# POWER.net
KiCad netlist of a schematic drawn in Altium Designer
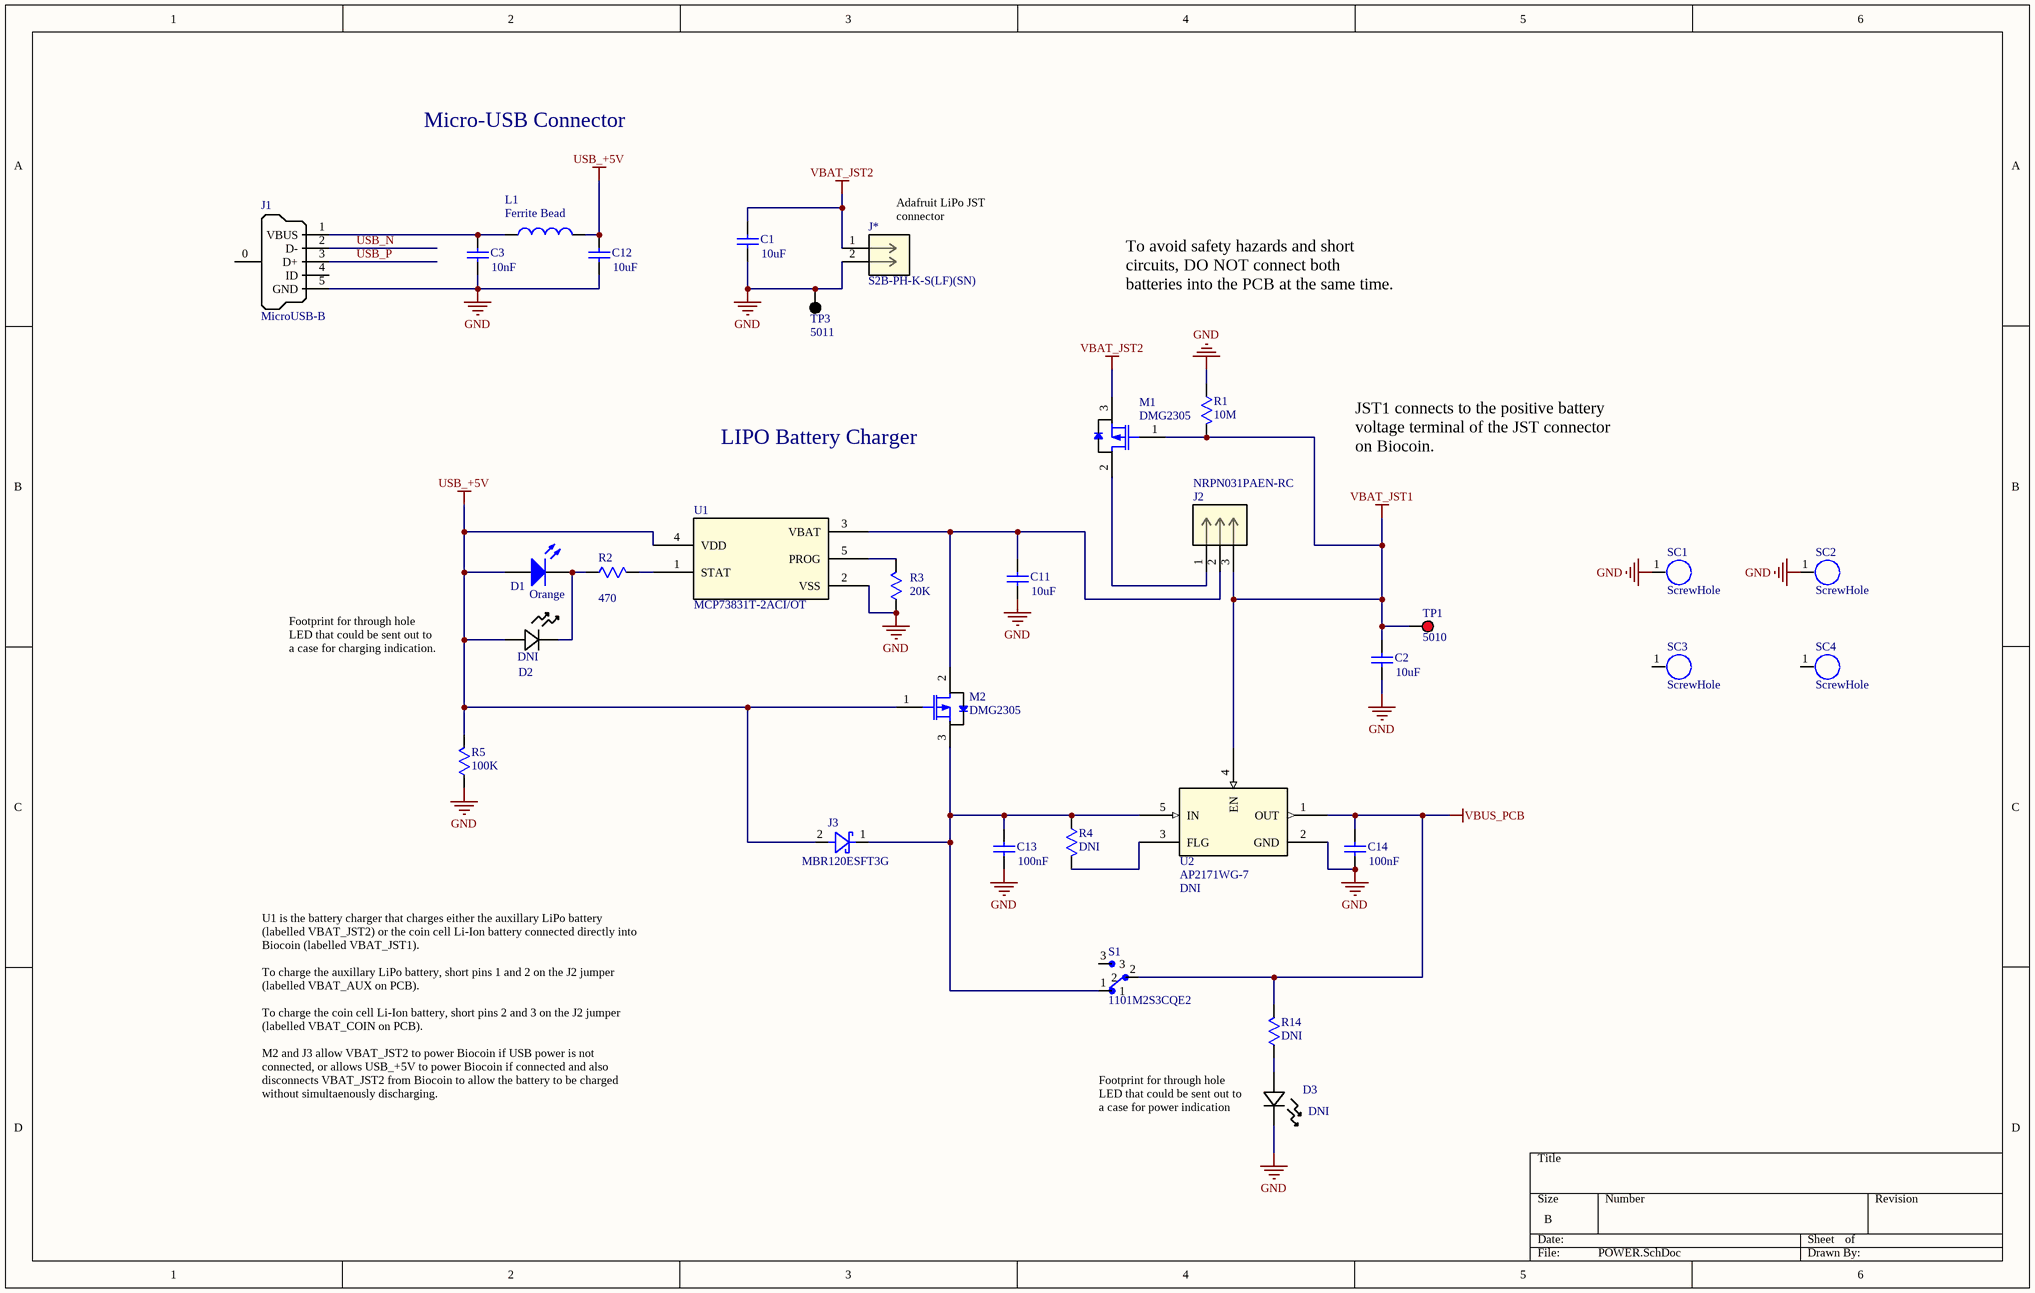
[diagram p0: POWER.SchDoc]

(export (version "E")
  (design (tool "Eeschema 10.0.6"))
  (components
    (comp (ref "C1")
      (value "10uF")
      (footprint "0805-CAP")
      (description "Multilayer Chip Capacitor")
      (fields (field (name "Comment") "CAP") (field (name "DESIGNER") "OMIGA"))
      (libsource (lib "Schlib") (part "CAP SMD"))
    )
    (comp (ref "C2")
      (value "10uF")
      (footprint "0805-CAP")
      (description "Multilayer Chip Capacitor")
      (fields (field (name "Comment") "CAP") (field (name "DESIGNER") "OMIGA"))
      (libsource (lib "Schlib") (part "CAP SMD"))
    )
    (comp (ref "C3")
      (value "10nF")
      (footprint "0805-CAP")
      (description "Multilayer Chip Capacitor")
      (fields (field (name "Comment") "CAP") (field (name "DESIGNER") "OMIGA"))
      (libsource (lib "Schlib") (part "CAP SMD"))
    )
    (comp (ref "C11")
      (value "10uF")
      (footprint "0805-CAP")
      (description "Multilayer Chip Capacitor")
      (fields (field (name "Comment") "CAP") (field (name "DESIGNER") "OMIGA"))
      (libsource (lib "Schlib") (part "CAP SMD"))
    )
    (comp (ref "C12")
      (value "10uF")
      (footprint "0805-CAP")
      (description "Multilayer Chip Capacitor")
      (fields (field (name "Comment") "CAP") (field (name "DESIGNER") "OMIGA"))
      (libsource (lib "Schlib") (part "CAP SMD"))
    )
    (comp (ref "C13")
      (value "100nF")
      (footprint "0805-CAP")
      (description "Multilayer Chip Capacitor")
      (fields (field (name "Comment") "CAP") (field (name "DESIGNER") "OMIGA"))
      (libsource (lib "Schlib") (part "CAP SMD"))
    )
    (comp (ref "C14")
      (value "100nF")
      (footprint "0805-CAP")
      (description "Multilayer Chip Capacitor")
      (fields (field (name "Comment") "CAP") (field (name "DESIGNER") "OMIGA"))
      (libsource (lib "Schlib") (part "CAP SMD"))
    )
    (comp (ref "D1")
      (value "LED SMD")
      (footprint "0805-LED")
      (description "Surface Mount Light Emitting Diode")
      (fields (field (name "LIGHT COLOR") "Orange"))
      (libsource (lib "Schlib") (part "LED SMD"))
    )
    (comp (ref "D2")
      (value "SLI-343V8RC3F")
      (footprint "LED_SLI-343D_ROM")
      (description "No Description Available")
      (fields
        (field (name "DO NOT INSTALL") "DNI")
        (field (name "COPYRIGHT") "Copyright (C) 2018 Accelerated Designs. All rights reserved")
      )
      (libsource (lib "Schlib") (part "SLI-343V8RC3F"))
    )
    (comp (ref "D3")
      (value "SLI-343V8RC3F")
      (footprint "LED_SLI-343D_ROM")
      (description "No Description Available")
      (fields
        (field (name "DO NOT INSTALL") "DNI")
        (field (name "COPYRIGHT") "Copyright (C) 2018 Accelerated Designs. All rights reserved")
      )
      (libsource (lib "Schlib") (part "SLI-343V8RC3F"))
    )
    (comp (ref "J*")
      (value "S2B-PH-K-S(LF)(SN)")
      (footprint "CONN_S2B-PH-K-S_JST")
      (description "Connector Header Through Hole, Right Angle 2 position 0.079\" (2.00mm)")
      (libsource (lib "Schlib") (part "S2B-PH-K-S(LF)(SN)"))
    )
    (comp (ref "J1")
      (value "MicroUSB-B")
      (footprint "MicroUSB-B")
      (description "Conn Micro USB Type B RCP 5")
      (fields (field (name "DESIGNER") "OMIGA"))
      (libsource (lib "Schlib") (part "MicroUSB-B"))
    )
    (comp (ref "J2")
      (value "NRPN031PAEN-RC")
      (footprint "CONN_NRPN031_SUL")
      (description "No Description Available")
      (fields (field (name "COPYRIGHT") "Copyright (C) 2022 Ultra Librarian. All rights reserved."))
      (libsource (lib "Schlib") (part "NRPN031PAEN-RC"))
    )
    (comp (ref "J3")
      (value "MBR120ESFT3G")
      (footprint "SDO_SOD-123FL_ONS-L")
      (description "Diode Schottky 1A Surface Mount SOD-123FL")
      (libsource (lib "Schlib") (part "SCHOTTKY"))
    )
    (comp (ref "L1")
      (value "Ferrite Bead")
      (footprint "0805-IND")
      (description "Surface Mount Inductor")
      (fields (field (name "Comment") "IND") (field (name "DESIGNER") "OMIGA"))
      (libsource (lib "Schlib") (part "IND SMD"))
    )
    (comp (ref "M1")
      (value "DMG2305")
      (footprint "SOT23-3-Lead")
      (description "P-Channel MOSFET DMG2305UX-13")
      (fields (field (name "DESIGNER") "OMIGA"))
      (libsource (lib "Schlib") (part "PMOS"))
    )
    (comp (ref "M2")
      (value "DMG2305")
      (footprint "SOT23-3-Lead")
      (description "P-Channel MOSFET DMG2305UX-13")
      (fields (field (name "DESIGNER") "OMIGA"))
      (libsource (lib "Schlib") (part "PMOS"))
    )
    (comp (ref "R1")
      (value "10M")
      (footprint "0805-RES")
      (description "Surface Mount Resistor")
      (fields (field (name "Comment") "RES") (field (name "DESIGNER") "OMIGA"))
      (libsource (lib "Schlib") (part "RES SMD"))
    )
    (comp (ref "R2")
      (value "470")
      (footprint "0805-RES")
      (description "Surface Mount Resistor")
      (fields (field (name "Comment") "RES") (field (name "DESIGNER") "OMIGA"))
      (libsource (lib "Schlib") (part "RES SMD"))
    )
    (comp (ref "R3")
      (value "20K")
      (footprint "0805-RES")
      (description "Surface Mount Resistor")
      (fields (field (name "Comment") "RES") (field (name "DESIGNER") "OMIGA"))
      (libsource (lib "Schlib") (part "RES SMD"))
    )
    (comp (ref "R4")
      (value "DNI")
      (footprint "0805-RES")
      (description "Surface Mount Resistor")
      (fields (field (name "Comment") "RES") (field (name "DESIGNER") "OMIGA"))
      (libsource (lib "Schlib") (part "RES SMD"))
    )
    (comp (ref "R5")
      (value "100K")
      (footprint "0805-RES")
      (description "Surface Mount Resistor")
      (fields (field (name "Comment") "RES") (field (name "DESIGNER") "OMIGA"))
      (libsource (lib "Schlib") (part "RES SMD"))
    )
    (comp (ref "R14")
      (value "DNI")
      (footprint "0805-RES")
      (description "Surface Mount Resistor")
      (fields (field (name "Comment") "RES") (field (name "DESIGNER") "OMIGA"))
      (libsource (lib "Schlib") (part "RES SMD"))
    )
    (comp (ref "S1")
      (value "1101M2S3CQE2")
      (footprint "SW_1101M2S3CQE2")
      (description "Slide Switch SPDT Through Hole")
      (fields (field (name "DIGI-KEY_PART_NUMBER") "CKN5001-ND") (field (name "MF") "C&K"))
      (libsource (lib "Schlib") (part "1101M2S3CQE2"))
    )
    (comp (ref "SC1")
      (value "ScrewHole")
      (footprint "ScrowHole")
      (description "Scrow Hole")
      (fields (field (name "DESIGNER") "OMIGA"))
      (libsource (lib "Schlib") (part "ScrewHole"))
    )
    (comp (ref "SC2")
      (value "ScrewHole")
      (footprint "ScrowHole")
      (description "Scrow Hole")
      (fields (field (name "DESIGNER") "OMIGA"))
      (libsource (lib "Schlib") (part "ScrewHole"))
    )
    (comp (ref "SC3")
      (value "ScrewHole")
      (footprint "ScrowHole")
      (description "Scrow Hole")
      (fields (field (name "DESIGNER") "OMIGA"))
      (libsource (lib "Schlib") (part "ScrewHole"))
    )
    (comp (ref "SC4")
      (value "ScrewHole")
      (footprint "ScrowHole")
      (description "Scrow Hole")
      (fields (field (name "DESIGNER") "OMIGA"))
      (libsource (lib "Schlib") (part "ScrewHole"))
    )
    (comp (ref "TP1")
      (value "5010")
      (footprint "KSTN-5010_V")
      (description "PC TEST POINT MULTIPURPOSE RED")
      (libsource (lib "Schlib") (part "Test Point Red"))
    )
    (comp (ref "TP3")
      (value "5011")
      (footprint "KSTN-5011_V")
      (description "PC TEST POINT MULTIPURPOSE BLACK")
      (libsource (lib "Schlib") (part "Test Point Black"))
    )
    (comp (ref "U1")
      (value "MCP73831T-2ACI/OT")
      (footprint "SOT23-5")
      (description "Charger IC Lithium Ion/Polymer SOT-23-5")
      (libsource (lib "Schlib") (part "MCP73831T-2ACI/OT"))
    )
    (comp (ref "U2")
      (value "AP2171WG-7")
      (footprint "SOT25_DIO-M")
      (description "No Description Available")
      (fields
        (field (name "ALTIUM_VALUE") "DNI")
        (field (name "COPYRIGHT") "Copyright (C) 2022 Ultra Librarian. All rights reserved.")
      )
      (libsource (lib "Schlib") (part "AP2171WG-7"))
    )
  )
  (nets
    (net (code "1") (name "/USB_N") (class "Default")
      (node (ref "J1") (pin "2") (pinfunction "D-_2") (pintype "passive"))
    )
    (net (code "2") (name "/USB_P") (class "Default")
      (node (ref "J1") (pin "3") (pinfunction "D+_3") (pintype "passive"))
    )
    (net (code "3") (name "GND") (class "Default")
      (node (ref "C1") (pin "1") (pinfunction "1_1") (pintype "passive"))
      (node (ref "C11") (pin "1") (pinfunction "1_1") (pintype "passive"))
      (node (ref "C12") (pin "1") (pinfunction "1_1") (pintype "passive"))
      (node (ref "C13") (pin "1") (pinfunction "1_1") (pintype "passive"))
      (node (ref "C14") (pin "1") (pinfunction "1_1") (pintype "passive"))
      (node (ref "C2") (pin "1") (pinfunction "1_1") (pintype "passive"))
      (node (ref "C3") (pin "1") (pinfunction "1_1") (pintype "passive"))
      (node (ref "D3") (pin "1") (pinfunction "1_1") (pintype "passive"))
      (node (ref "J*") (pin "2") (pinfunction "2_2") (pintype "passive"))
      (node (ref "J1") (pin "5") (pinfunction "GND_5") (pintype "power_in"))
      (node (ref "R1") (pin "1") (pinfunction "1_1") (pintype "passive"))
      (node (ref "R3") (pin "1") (pinfunction "1_1") (pintype "passive"))
      (node (ref "R5") (pin "1") (pinfunction "1_1") (pintype "passive"))
      (node (ref "SC1") (pin "1") (pinfunction "1_1") (pintype "passive"))
      (node (ref "SC2") (pin "1") (pinfunction "1_1") (pintype "passive"))
      (node (ref "TP3") (pin "1") (pinfunction "1_1") (pintype "passive"))
      (node (ref "U1") (pin "2") (pinfunction "VSS_2") (pintype "passive"))
      (node (ref "U2") (pin "2") (pinfunction "GND_2") (pintype "power_in"))
    )
    (net (code "4") (name "Net-(D1-K)") (class "Default")
      (node (ref "D1") (pin "2") (pinfunction "K_2") (pintype "passive"))
      (node (ref "D2") (pin "1") (pinfunction "1_1") (pintype "passive"))
      (node (ref "R2") (pin "1") (pinfunction "1_1") (pintype "passive"))
    )
    (net (code "5") (name "Net-(D3-Pad2)") (class "Default")
      (node (ref "D3") (pin "2") (pinfunction "2_2") (pintype "passive"))
      (node (ref "R14") (pin "1") (pinfunction "1_1") (pintype "passive"))
    )
    (net (code "6") (name "Net-(J1-VBUS)") (class "Default")
      (node (ref "C3") (pin "2") (pinfunction "2_2") (pintype "passive"))
      (node (ref "J1") (pin "1") (pinfunction "VBUS_1") (pintype "power_in"))
      (node (ref "L1") (pin "1") (pinfunction "1_1") (pintype "passive"))
    )
    (net (code "7") (name "Net-(J3-11)") (class "Default")
      (node (ref "C13") (pin "2") (pinfunction "2_2") (pintype "passive"))
      (node (ref "J3") (pin "1") (pinfunction "11_1") (pintype "passive"))
      (node (ref "M2") (pin "3") (pinfunction "D_3") (pintype "passive"))
      (node (ref "R4") (pin "1") (pinfunction "1_1") (pintype "passive"))
      (node (ref "S1") (pin "1") (pinfunction "1_1") (pintype "passive"))
      (node (ref "U2") (pin "5") (pinfunction "IN_5") (pintype "input"))
    )
    (net (code "8") (name "Net-(M1-S)") (class "Default")
      (node (ref "J2") (pin "1") (pinfunction "1_1") (pintype "passive"))
      (node (ref "M1") (pin "2") (pinfunction "S_2") (pintype "passive"))
    )
    (net (code "9") (name "Net-(M2-S)") (class "Default")
      (node (ref "C11") (pin "2") (pinfunction "2_2") (pintype "passive"))
      (node (ref "J2") (pin "2") (pinfunction "2_2") (pintype "passive"))
      (node (ref "M2") (pin "2") (pinfunction "S_2") (pintype "passive"))
      (node (ref "U1") (pin "3") (pinfunction "VBAT_3") (pintype "passive"))
    )
    (net (code "10") (name "Net-(U1-PROG)") (class "Default")
      (node (ref "R3") (pin "2") (pinfunction "2_2") (pintype "passive"))
      (node (ref "U1") (pin "5") (pinfunction "PROG_5") (pintype "passive"))
    )
    (net (code "11") (name "Net-(U1-STAT)") (class "Default")
      (node (ref "R2") (pin "2") (pinfunction "2_2") (pintype "passive"))
      (node (ref "U1") (pin "1") (pinfunction "STAT_1") (pintype "passive"))
    )
    (net (code "12") (name "Net-(U2-FLG)") (class "Default")
      (node (ref "R4") (pin "2") (pinfunction "2_2") (pintype "passive"))
      (node (ref "U2") (pin "3") (pinfunction "FLG_3") (pintype "passive"))
    )
    (net (code "13") (name "USB_+5V") (class "Default")
      (node (ref "C12") (pin "2") (pinfunction "2_2") (pintype "passive"))
      (node (ref "D1") (pin "1") (pinfunction "A_1") (pintype "passive"))
      (node (ref "D2") (pin "2") (pinfunction "2_2") (pintype "passive"))
      (node (ref "J3") (pin "2") (pinfunction "12_2") (pintype "passive"))
      (node (ref "L1") (pin "2") (pinfunction "2_2") (pintype "passive"))
      (node (ref "M2") (pin "1") (pinfunction "G_1") (pintype "passive"))
      (node (ref "R5") (pin "2") (pinfunction "2_2") (pintype "passive"))
      (node (ref "U1") (pin "4") (pinfunction "VDD_4") (pintype "passive"))
    )
    (net (code "14") (name "VBAT_JST1") (class "Default")
      (node (ref "C2") (pin "2") (pinfunction "2_2") (pintype "passive"))
      (node (ref "J2") (pin "3") (pinfunction "3_3") (pintype "passive"))
      (node (ref "M1") (pin "1") (pinfunction "G_1") (pintype "passive"))
      (node (ref "R1") (pin "2") (pinfunction "2_2") (pintype "passive"))
      (node (ref "TP1") (pin "1") (pinfunction "1_1") (pintype "passive"))
      (node (ref "U2") (pin "4") (pinfunction "EN_4") (pintype "input"))
    )
    (net (code "15") (name "VBAT_JST2") (class "Default")
      (node (ref "C1") (pin "2") (pinfunction "2_2") (pintype "passive"))
      (node (ref "J*") (pin "1") (pinfunction "1_1") (pintype "passive"))
      (node (ref "M1") (pin "3") (pinfunction "D_3") (pintype "passive"))
    )
    (net (code "16") (name "VBUS_PCB") (class "Default")
      (node (ref "C14") (pin "2") (pinfunction "2_2") (pintype "passive"))
      (node (ref "R14") (pin "2") (pinfunction "2_2") (pintype "passive"))
      (node (ref "S1") (pin "2") (pinfunction "2_2") (pintype "passive"))
      (node (ref "U2") (pin "1") (pinfunction "OUT_1") (pintype "output"))
    )
    (net (code "17") (name "unconnected-(J1-ID-Pad4)") (class "Default")
      (node (ref "J1") (pin "4") (pinfunction "ID_4") (pintype "passive"))
    )
    (net (code "18") (name "unconnected-(J1-Shell-Pad0)") (class "Default")
      (node (ref "J1") (pin "0") (pinfunction "Shell_0") (pintype "passive"))
    )
    (net (code "19") (name "unconnected-(S1-Pad3)") (class "Default")
      (node (ref "S1") (pin "3") (pinfunction "3_3") (pintype "passive"))
    )
    (net (code "20") (name "unconnected-(SC3-Pad1)") (class "Default")
      (node (ref "SC3") (pin "1") (pinfunction "1_1") (pintype "passive"))
    )
    (net (code "21") (name "unconnected-(SC4-Pad1)") (class "Default")
      (node (ref "SC4") (pin "1") (pinfunction "1_1") (pintype "passive"))
    )
  )
)
